# Brethalyzer_schematic.net
KiCad netlist of a schematic drawn in Altium Designer
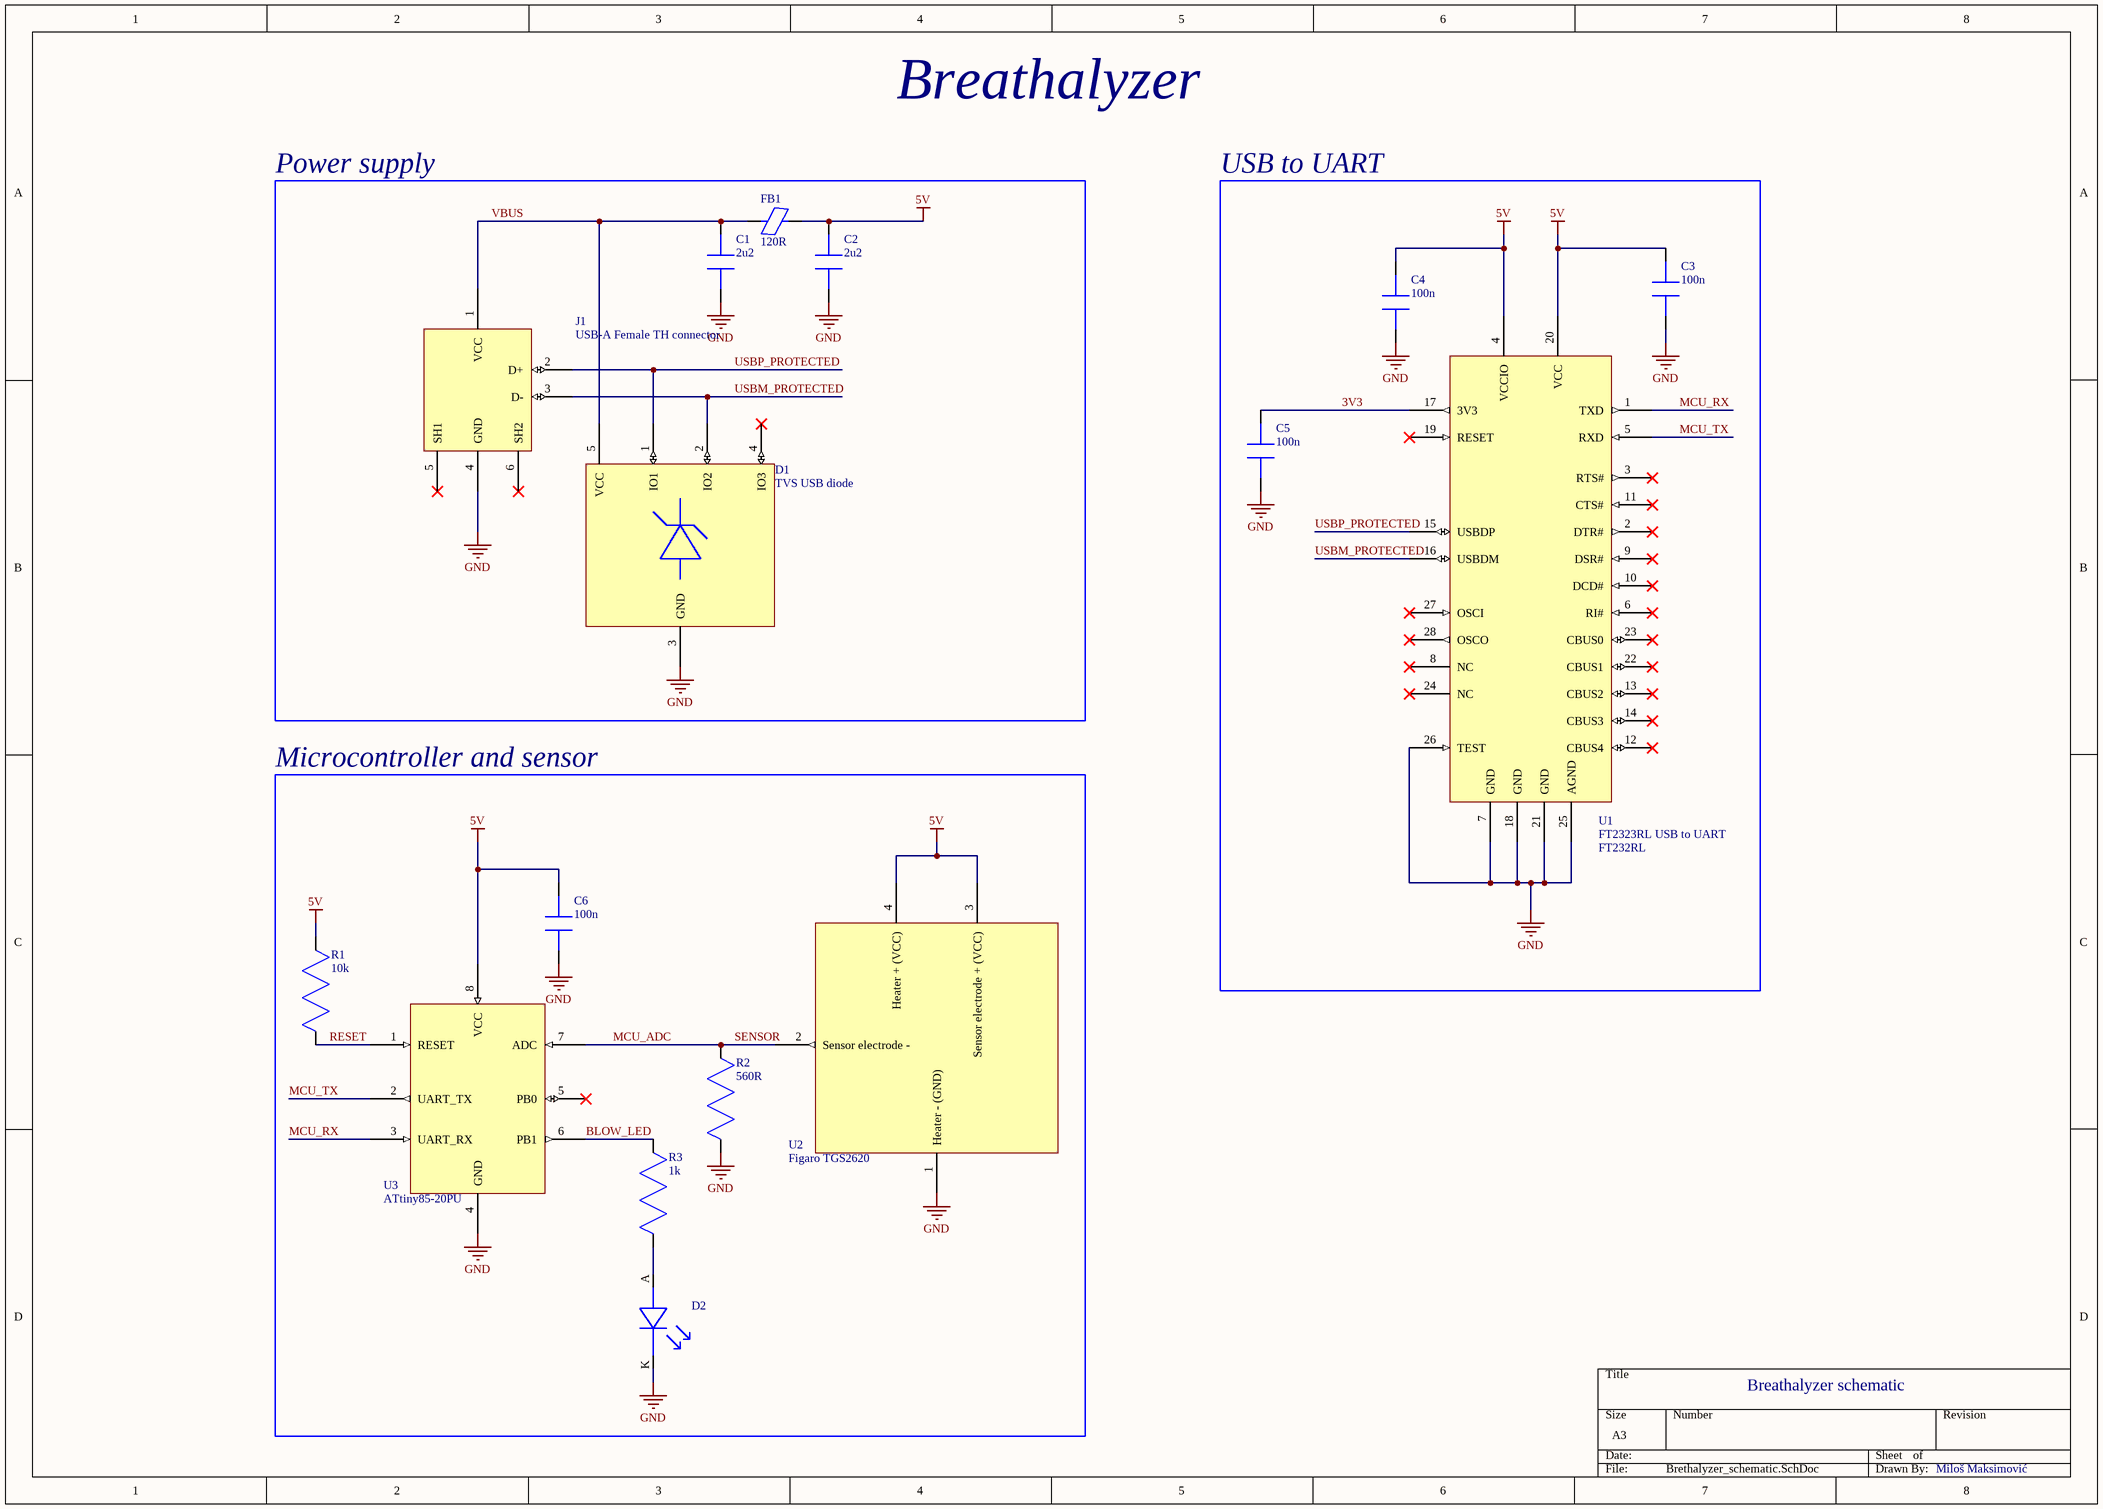
[diagram p0: Brethalyzer_schematic.SchDoc]

(export (version "E")
  (design (tool "Eeschema 10.0.6"))
  (components
    (comp (ref "C1")
      (value "2u2")
      (footprint "Capacitor 0805")
      (description "0805 SMD Capacitor")
      (libsource (lib "alcotest_sch_lib") (part "0805 Capacitor"))
    )
    (comp (ref "C2")
      (value "2u2")
      (footprint "Capacitor 0805")
      (description "0805 SMD Capacitor")
      (libsource (lib "alcotest_sch_lib") (part "0805 Capacitor"))
    )
    (comp (ref "C3")
      (value "100n")
      (footprint "Capacitor 0805")
      (description "0805 SMD Capacitor")
      (libsource (lib "alcotest_sch_lib") (part "0805 Capacitor"))
    )
    (comp (ref "C4")
      (value "100n")
      (footprint "Capacitor 0805")
      (description "0805 SMD Capacitor")
      (libsource (lib "alcotest_sch_lib") (part "0805 Capacitor"))
    )
    (comp (ref "C5")
      (value "100n")
      (footprint "Capacitor 0805")
      (description "0805 SMD Capacitor")
      (libsource (lib "alcotest_sch_lib") (part "0805 Capacitor"))
    )
    (comp (ref "C6")
      (value "100n")
      (footprint "Capacitor 0805")
      (description "0805 SMD Capacitor")
      (libsource (lib "alcotest_sch_lib") (part "0805 Capacitor"))
    )
    (comp (ref "D1")
      (value "TVS USB diode")
      (footprint "TVS diode")
      (description "TVS DIODE 5.5VWM SOT5")
      (fields (field (name "MANUFACTURER") "Texas Instruments"))
      (libsource (lib "alcotest_sch_lib") (part "TVS_diode"))
    )
    (comp (ref "D2")
      (value "0603 SMD LED")
      (footprint "0603 LED")
      (libsource (lib "alcotest_sch_lib") (part "SMD0603_LED"))
    )
    (comp (ref "FB1")
      (value "120R")
      (footprint "Ferrite bead")
      (description "Ferrite Beads 0.6mm x 0.3mm x 0.3mm, -55 to +125 degC, 200mA, 120ohm, 390mohm")
      (fields (field (name "MANUFACTURER") "TDK") (field (name "Comment") "Ferrite bead"))
      (libsource (lib "alcotest_sch_lib") (part "Ferrite bead"))
    )
    (comp (ref "J1")
      (value "USB-A Female TH connector")
      (footprint "USB A Female TH connector")
      (libsource (lib "alcotest_sch_lib") (part "USB-A Female"))
    )
    (comp (ref "R1")
      (value "10k")
      (footprint "Resistor 0805")
      (description "0805 SMD resistor")
      (libsource (lib "alcotest_sch_lib") (part "0805 Resistor"))
    )
    (comp (ref "R2")
      (value "560R")
      (footprint "Resistor 0805")
      (description "0805 SMD resistor")
      (libsource (lib "alcotest_sch_lib") (part "0805 Resistor"))
    )
    (comp (ref "R3")
      (value "1k")
      (footprint "Resistor 0805")
      (description "0805 SMD resistor")
      (libsource (lib "alcotest_sch_lib") (part "0805 Resistor"))
    )
    (comp (ref "U1")
      (value "FT2323RL USB to UART")
      (footprint "SOP28")
      (description "USB Bridge, USB to UART USB 2.0 UART Interface 28-SSOP")
      (fields (field (name "MANUFACTURER") "FTDI") (field (name "MANUFACTURER PRODUCT NUMBER") "FT232RL"))
      (libsource (lib "alcotest_sch_lib") (part "FT2323RL"))
    )
    (comp (ref "U2")
      (value "Figaro TGS2620")
      (footprint "TGS2620")
      (description "Figaro TGS2620 gas sensor")
      (fields
        (field (name "MANUFACTURER") "Figaro")
        (field (name "MANUFACTURER PRODUCT NUMBER") "Figaro TGS2620")
      )
      (libsource (lib "alcotest_sch_lib") (part "TGS2620"))
    )
    (comp (ref "U3")
      (value "ATtiny85-20PU")
      (footprint "DIP-8")
      (fields (field (name "MANUFACTURER") "Microchip Technology"))
      (libsource (lib "alcotest_sch_lib") (part "ATtiny85"))
    )
  )
  (nets
    (net (code "1") (name "/3V3") (class "Default")
      (node (ref "C5") (pin "1") (pinfunction "1_1") (pintype "passive"))
      (node (ref "U1") (pin "17") (pinfunction "3V3_17") (pintype "output"))
    )
    (net (code "2") (name "/BLOW_LED") (class "Default")
      (node (ref "R3") (pin "2") (pinfunction "2_2") (pintype "passive"))
      (node (ref "U3") (pin "6") (pinfunction "PB1_6") (pintype "output"))
    )
    (net (code "3") (name "/MCU_ADC") (class "Default")
      (node (ref "R2") (pin "2") (pinfunction "2_2") (pintype "passive"))
      (node (ref "U2") (pin "2") (pinfunction "Sensor_electrode_-_2") (pintype "output"))
      (node (ref "U3") (pin "7") (pinfunction "ADC_7") (pintype "input"))
    )
    (net (code "4") (name "/MCU_RX") (class "Default")
      (node (ref "U1") (pin "1") (pinfunction "TXD_1") (pintype "output"))
      (node (ref "U3") (pin "3") (pinfunction "UART_RX_3") (pintype "input"))
    )
    (net (code "5") (name "/MCU_TX") (class "Default")
      (node (ref "U1") (pin "5") (pinfunction "RXD_5") (pintype "input"))
      (node (ref "U3") (pin "2") (pinfunction "UART_TX_2") (pintype "output"))
    )
    (net (code "6") (name "/RESET") (class "Default")
      (node (ref "R1") (pin "1") (pinfunction "1_1") (pintype "passive"))
      (node (ref "U3") (pin "1") (pinfunction "RESET_1") (pintype "input"))
    )
    (net (code "7") (name "/USBM_PROTECTED") (class "Default")
      (node (ref "D1") (pin "2") (pinfunction "IO2_2") (pintype "bidirectional"))
      (node (ref "J1") (pin "3") (pinfunction "D-_3") (pintype "bidirectional"))
      (node (ref "U1") (pin "16") (pinfunction "USBDM_16") (pintype "bidirectional"))
    )
    (net (code "8") (name "/USBP_PROTECTED") (class "Default")
      (node (ref "D1") (pin "1") (pinfunction "IO1_1") (pintype "bidirectional"))
      (node (ref "J1") (pin "2") (pinfunction "D+_2") (pintype "bidirectional"))
      (node (ref "U1") (pin "15") (pinfunction "USBDP_15") (pintype "bidirectional"))
    )
    (net (code "9") (name "/VBUS") (class "Default")
      (node (ref "C1") (pin "1") (pinfunction "1_1") (pintype "passive"))
      (node (ref "D1") (pin "5") (pinfunction "VCC_5") (pintype "power_in"))
      (node (ref "FB1") (pin "1") (pinfunction "1_1") (pintype "passive"))
      (node (ref "J1") (pin "1") (pinfunction "VCC_1") (pintype "power_in"))
    )
    (net (code "10") (name "5V") (class "Default")
      (node (ref "C2") (pin "1") (pinfunction "1_1") (pintype "passive"))
      (node (ref "C3") (pin "1") (pinfunction "1_1") (pintype "passive"))
      (node (ref "C4") (pin "1") (pinfunction "1_1") (pintype "passive"))
      (node (ref "C6") (pin "1") (pinfunction "1_1") (pintype "passive"))
      (node (ref "FB1") (pin "2") (pinfunction "2_2") (pintype "passive"))
      (node (ref "R1") (pin "2") (pinfunction "2_2") (pintype "passive"))
      (node (ref "U1") (pin "20") (pinfunction "VCC_20") (pintype "power_in"))
      (node (ref "U1") (pin "4") (pinfunction "VCCIO_4") (pintype "power_in"))
      (node (ref "U2") (pin "3") (pinfunction "Sensor_electrode_+_(VCC)_3") (pintype "power_in"))
      (node (ref "U2") (pin "4") (pinfunction "Heater_+_(VCC)_4") (pintype "power_in"))
      (node (ref "U3") (pin "8") (pinfunction "VCC_8") (pintype "input"))
    )
    (net (code "11") (name "GND") (class "Default")
      (node (ref "C1") (pin "2") (pinfunction "2_2") (pintype "passive"))
      (node (ref "C2") (pin "2") (pinfunction "2_2") (pintype "passive"))
      (node (ref "C3") (pin "2") (pinfunction "2_2") (pintype "passive"))
      (node (ref "C4") (pin "2") (pinfunction "2_2") (pintype "passive"))
      (node (ref "C5") (pin "2") (pinfunction "2_2") (pintype "passive"))
      (node (ref "C6") (pin "2") (pinfunction "2_2") (pintype "passive"))
      (node (ref "D1") (pin "3") (pinfunction "GND_3") (pintype "power_in"))
      (node (ref "D2") (pin "K") (pinfunction "K_K") (pintype "passive"))
      (node (ref "J1") (pin "4") (pinfunction "GND_4") (pintype "power_in"))
      (node (ref "R2") (pin "1") (pinfunction "1_1") (pintype "passive"))
      (node (ref "U1") (pin "18") (pinfunction "GND_18") (pintype "power_in"))
      (node (ref "U1") (pin "21") (pinfunction "GND_21") (pintype "power_in"))
      (node (ref "U1") (pin "25") (pinfunction "AGND_25") (pintype "power_in"))
      (node (ref "U1") (pin "26") (pinfunction "TEST_26") (pintype "input"))
      (node (ref "U1") (pin "7") (pinfunction "GND_7") (pintype "power_in"))
      (node (ref "U2") (pin "1") (pinfunction "Heater_-_(GND)_1") (pintype "power_in"))
      (node (ref "U3") (pin "4") (pinfunction "GND_4") (pintype "power_in"))
    )
    (net (code "12") (name "Net-(D2-PadA)") (class "Default")
      (node (ref "D2") (pin "A") (pinfunction "A_A") (pintype "passive"))
      (node (ref "R3") (pin "1") (pinfunction "1_1") (pintype "passive"))
    )
    (net (code "13") (name "unconnected-(D1-IO3-Pad4)") (class "Default")
      (node (ref "D1") (pin "4") (pinfunction "IO3_4") (pintype "bidirectional+no_connect"))
    )
    (net (code "14") (name "unconnected-(J1-SH1-Pad5)") (class "Default")
      (node (ref "J1") (pin "5") (pinfunction "SH1_5") (pintype "power_in+no_connect"))
    )
    (net (code "15") (name "unconnected-(J1-SH2-Pad6)") (class "Default")
      (node (ref "J1") (pin "6") (pinfunction "SH2_6") (pintype "power_in+no_connect"))
    )
    (net (code "16") (name "unconnected-(U1-CBUS0-Pad23)") (class "Default")
      (node (ref "U1") (pin "23") (pinfunction "CBUS0_23") (pintype "bidirectional+no_connect"))
    )
    (net (code "17") (name "unconnected-(U1-CBUS1-Pad22)") (class "Default")
      (node (ref "U1") (pin "22") (pinfunction "CBUS1_22") (pintype "bidirectional+no_connect"))
    )
    (net (code "18") (name "unconnected-(U1-CBUS2-Pad13)") (class "Default")
      (node (ref "U1") (pin "13") (pinfunction "CBUS2_13") (pintype "bidirectional+no_connect"))
    )
    (net (code "19") (name "unconnected-(U1-CBUS3-Pad14)") (class "Default")
      (node (ref "U1") (pin "14") (pinfunction "CBUS3_14") (pintype "bidirectional+no_connect"))
    )
    (net (code "20") (name "unconnected-(U1-CBUS4-Pad12)") (class "Default")
      (node (ref "U1") (pin "12") (pinfunction "CBUS4_12") (pintype "bidirectional+no_connect"))
    )
    (net (code "21") (name "unconnected-(U1-CTS#-Pad11)") (class "Default")
      (node (ref "U1") (pin "11") (pinfunction "CTS#_11") (pintype "input+no_connect"))
    )
    (net (code "22") (name "unconnected-(U1-DCD#-Pad10)") (class "Default")
      (node (ref "U1") (pin "10") (pinfunction "DCD#_10") (pintype "input+no_connect"))
    )
    (net (code "23") (name "unconnected-(U1-DSR#-Pad9)") (class "Default")
      (node (ref "U1") (pin "9") (pinfunction "DSR#_9") (pintype "input+no_connect"))
    )
    (net (code "24") (name "unconnected-(U1-DTR#-Pad2)") (class "Default")
      (node (ref "U1") (pin "2") (pinfunction "DTR#_2") (pintype "output+no_connect"))
    )
    (net (code "25") (name "unconnected-(U1-NC-Pad8)") (class "Default")
      (node (ref "U1") (pin "8") (pinfunction "NC_8") (pintype "passive+no_connect"))
    )
    (net (code "26") (name "unconnected-(U1-NC-Pad24)") (class "Default")
      (node (ref "U1") (pin "24") (pinfunction "NC_24") (pintype "passive+no_connect"))
    )
    (net (code "27") (name "unconnected-(U1-OSCI-Pad27)") (class "Default")
      (node (ref "U1") (pin "27") (pinfunction "OSCI_27") (pintype "input+no_connect"))
    )
    (net (code "28") (name "unconnected-(U1-OSCO-Pad28)") (class "Default")
      (node (ref "U1") (pin "28") (pinfunction "OSCO_28") (pintype "output+no_connect"))
    )
    (net (code "29") (name "unconnected-(U1-RESET-Pad19)") (class "Default")
      (node (ref "U1") (pin "19") (pinfunction "RESET_19") (pintype "input+no_connect"))
    )
    (net (code "30") (name "unconnected-(U1-RI#-Pad6)") (class "Default")
      (node (ref "U1") (pin "6") (pinfunction "RI#_6") (pintype "input+no_connect"))
    )
    (net (code "31") (name "unconnected-(U1-RTS#-Pad3)") (class "Default")
      (node (ref "U1") (pin "3") (pinfunction "RTS#_3") (pintype "output+no_connect"))
    )
    (net (code "32") (name "unconnected-(U3-PB0-Pad5)") (class "Default")
      (node (ref "U3") (pin "5") (pinfunction "PB0_5") (pintype "bidirectional+no_connect"))
    )
  )
)
